# Sheet2.net
KiCad netlist of a schematic drawn in Altium Designer
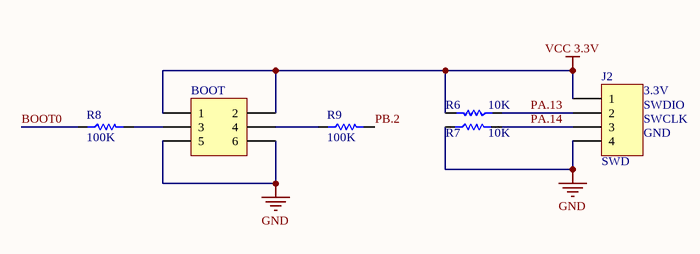
[diagram p0: Sheet2.SchDoc]

(export (version "E")
  (design (tool "Eeschema 10.0.6"))
  (components
    (comp (ref "BOOT")
      (value "Header 3X2")
      (footprint "HDR2X3")
      (description "Header, 3-Pin, Dual row")
      (fields (field (name "PUBLISHER") "Altium Limited"))
      (libsource (lib "Miscellaneous Connectors") (part "Header 3X2"))
    )
    (comp (ref "J2")
      (value "SWD")
      (footprint "HDR1X4")
      (description "Header, 4-Pin")
      (fields (field (name "PUBLISHER") "Altium Limited"))
      (libsource (lib "Miscellaneous Connectors") (part "Header 4"))
    )
    (comp (ref "R6")
      (value "10K")
      (footprint "SMD_RES_0805")
      (description "Resistor")
      (fields (field (name "TOLERANCE") "5%") (field (name "POWER") "1/8 W"))
      (libsource (lib "DDEmS Library") (part "Resistor"))
    )
    (comp (ref "R7")
      (value "10K")
      (footprint "SMD_RES_0805")
      (description "Resistor")
      (fields (field (name "TOLERANCE") "5%") (field (name "POWER") "1/8 W"))
      (libsource (lib "DDEmS Library") (part "Resistor"))
    )
    (comp (ref "R8")
      (value "100K")
      (footprint "SMD_RES_0805")
      (description "Resistor")
      (fields (field (name "TOLERANCE") "5%") (field (name "POWER") "1/8 W"))
      (libsource (lib "DDEmS Library") (part "Resistor"))
    )
    (comp (ref "R9")
      (value "100K")
      (footprint "SMD_RES_0805")
      (description "Resistor")
      (fields (field (name "TOLERANCE") "5%") (field (name "POWER") "1/8 W"))
      (libsource (lib "DDEmS Library") (part "Resistor"))
    )
  )
  (nets
    (net (code "1") (name "/BOOT0") (class "Default")
      (node (ref "R8") (pin "1") (pinfunction "1_1") (pintype "passive"))
    )
    (net (code "2") (name "/PA.13") (class "Default")
      (node (ref "J2") (pin "2") (pinfunction "2_2") (pintype "passive"))
      (node (ref "R6") (pin "1") (pinfunction "1_1") (pintype "passive"))
    )
    (net (code "3") (name "/PA.14") (class "Default")
      (node (ref "J2") (pin "3") (pinfunction "3_3") (pintype "passive"))
      (node (ref "R7") (pin "2") (pinfunction "2_2") (pintype "passive"))
    )
    (net (code "4") (name "/PB.2") (class "Default")
      (node (ref "R9") (pin "2") (pinfunction "2_2") (pintype "passive"))
    )
    (net (code "5") (name "GND") (class "Default")
      (node (ref "BOOT") (pin "5") (pinfunction "5_5") (pintype "passive"))
      (node (ref "BOOT") (pin "6") (pinfunction "6_6") (pintype "passive"))
      (node (ref "J2") (pin "4") (pinfunction "4_4") (pintype "passive"))
      (node (ref "R7") (pin "1") (pinfunction "1_1") (pintype "passive"))
    )
    (net (code "6") (name "Net-(BOOT-Pad3)") (class "Default")
      (node (ref "BOOT") (pin "3") (pinfunction "3_3") (pintype "passive"))
      (node (ref "R8") (pin "2") (pinfunction "2_2") (pintype "passive"))
    )
    (net (code "7") (name "Net-(BOOT-Pad4)") (class "Default")
      (node (ref "BOOT") (pin "4") (pinfunction "4_4") (pintype "passive"))
      (node (ref "R9") (pin "1") (pinfunction "1_1") (pintype "passive"))
    )
    (net (code "8") (name "VCC 3.3V") (class "Default")
      (node (ref "BOOT") (pin "1") (pinfunction "1_1") (pintype "passive"))
      (node (ref "BOOT") (pin "2") (pinfunction "2_2") (pintype "passive"))
      (node (ref "J2") (pin "1") (pinfunction "1_1") (pintype "passive"))
      (node (ref "R6") (pin "2") (pinfunction "2_2") (pintype "passive"))
    )
  )
)
